# Driver_Mosfet.net
KiCad netlist of a schematic drawn in Altium Designer
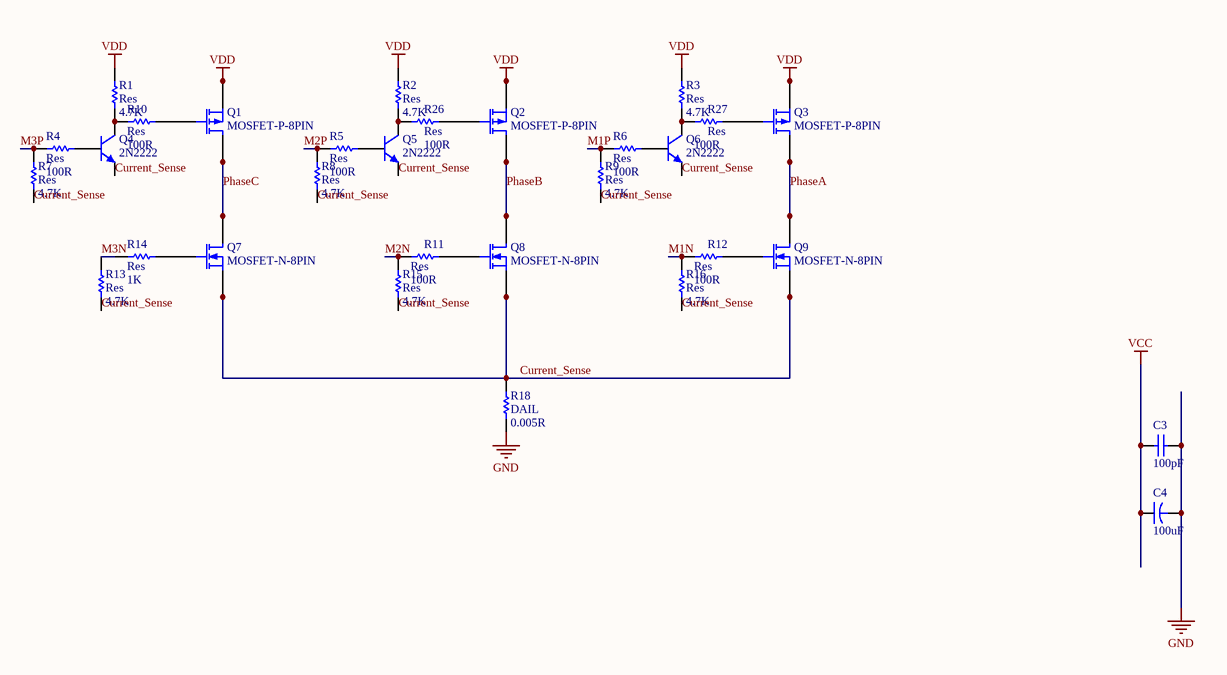
[diagram p0: Driver_Mosfet.SchDoc]

(export (version "E")
  (design (tool "Eeschema 10.0.6"))
  (components
    (comp (ref "C3")
      (value "100pF")
      (footprint "2012[0805]")
      (description "Capacitor")
      (fields (field (name "Comment") "Cap_UP") (field (name "PUBLISHER") "Altium Limited"))
      (libsource (lib "KN2CLib") (part "Cap_UP"))
    )
    (comp (ref "C4")
      (value "100uF")
      (footprint "7343")
      (description "Capacitor")
      (fields (field (name "Comment") "Cap_El") (field (name "PUBLISHER") "Altium Limited"))
      (libsource (lib "KN2CLib") (part "Cap_El"))
    )
    (comp (ref "Q1")
      (value "MOSFET-P-8PIN")
      (footprint "SO-8_N")
      (description "P-Channel MOSFET")
      (fields (field (name "PUBLISHER") "Altium Limited"))
      (libsource (lib "KN2CLib") (part "MOSFET-P-8PIN"))
    )
    (comp (ref "Q2")
      (value "MOSFET-P-8PIN")
      (footprint "SO-8_N")
      (description "P-Channel MOSFET")
      (fields (field (name "PUBLISHER") "Altium Limited"))
      (libsource (lib "KN2CLib") (part "MOSFET-P-8PIN"))
    )
    (comp (ref "Q3")
      (value "MOSFET-P-8PIN")
      (footprint "SO-8_N")
      (description "P-Channel MOSFET")
      (fields (field (name "PUBLISHER") "Altium Limited"))
      (libsource (lib "KN2CLib") (part "MOSFET-P-8PIN"))
    )
    (comp (ref "Q4")
      (value "2N2222")
      (footprint "SOT-23")
      (description "NPN Bipolar Transistor")
      (fields (field (name "PUBLISHER") "Altium Limited"))
      (libsource (lib "KN2CLib") (part "2N2222"))
    )
    (comp (ref "Q5")
      (value "2N2222")
      (footprint "SOT-23")
      (description "NPN Bipolar Transistor")
      (fields (field (name "PUBLISHER") "Altium Limited"))
      (libsource (lib "KN2CLib") (part "2N2222"))
    )
    (comp (ref "Q6")
      (value "2N2222")
      (footprint "SOT-23")
      (description "NPN Bipolar Transistor")
      (fields (field (name "PUBLISHER") "Altium Limited"))
      (libsource (lib "KN2CLib") (part "2N2222"))
    )
    (comp (ref "Q7")
      (value "MOSFET-N-8PIN")
      (footprint "SO-8_N")
      (description "N-Channel MOSFET")
      (fields (field (name "PUBLISHER") "Altium Limited"))
      (libsource (lib "KN2CLib") (part "MOSFET-N-8PIN"))
    )
    (comp (ref "Q8")
      (value "MOSFET-N-8PIN")
      (footprint "SO-8_N")
      (description "N-Channel MOSFET")
      (fields (field (name "PUBLISHER") "Altium Limited"))
      (libsource (lib "KN2CLib") (part "MOSFET-N-8PIN"))
    )
    (comp (ref "Q9")
      (value "MOSFET-N-8PIN")
      (footprint "SO-8_N")
      (description "N-Channel MOSFET")
      (fields (field (name "PUBLISHER") "Altium Limited"))
      (libsource (lib "KN2CLib") (part "MOSFET-N-8PIN"))
    )
    (comp (ref "R1")
      (value "Res")
      (footprint "2012[0805]")
      (description "Semiconductor Resistor")
      (fields (field (name "ALTIUM_VALUE") "4.7K") (field (name "PUBLISHER") "Altium Limited"))
      (libsource (lib "KN2CLib") (part "=Value"))
    )
    (comp (ref "R2")
      (value "Res")
      (footprint "2012[0805]")
      (description "Semiconductor Resistor")
      (fields (field (name "ALTIUM_VALUE") "4.7K") (field (name "PUBLISHER") "Altium Limited"))
      (libsource (lib "KN2CLib") (part "=Value"))
    )
    (comp (ref "R3")
      (value "Res")
      (footprint "2012[0805]")
      (description "Semiconductor Resistor")
      (fields (field (name "ALTIUM_VALUE") "4.7K") (field (name "PUBLISHER") "Altium Limited"))
      (libsource (lib "KN2CLib") (part "=Value"))
    )
    (comp (ref "R4")
      (value "Res")
      (footprint "2012[0805]")
      (description "Semiconductor Resistor")
      (fields (field (name "ALTIUM_VALUE") "100R") (field (name "PUBLISHER") "Altium Limited"))
      (libsource (lib "KN2CLib") (part "=Value"))
    )
    (comp (ref "R5")
      (value "Res")
      (footprint "2012[0805]")
      (description "Semiconductor Resistor")
      (fields (field (name "ALTIUM_VALUE") "100R") (field (name "PUBLISHER") "Altium Limited"))
      (libsource (lib "KN2CLib") (part "=Value"))
    )
    (comp (ref "R6")
      (value "Res")
      (footprint "2012[0805]")
      (description "Semiconductor Resistor")
      (fields (field (name "ALTIUM_VALUE") "100R") (field (name "PUBLISHER") "Altium Limited"))
      (libsource (lib "KN2CLib") (part "=Value"))
    )
    (comp (ref "R7")
      (value "Res")
      (footprint "2012[0805]")
      (description "Semiconductor Resistor")
      (fields (field (name "ALTIUM_VALUE") "4.7K") (field (name "PUBLISHER") "Altium Limited"))
      (libsource (lib "KN2CLib") (part "=Value"))
    )
    (comp (ref "R8")
      (value "Res")
      (footprint "2012[0805]")
      (description "Semiconductor Resistor")
      (fields (field (name "ALTIUM_VALUE") "4.7K") (field (name "PUBLISHER") "Altium Limited"))
      (libsource (lib "KN2CLib") (part "=Value"))
    )
    (comp (ref "R9")
      (value "Res")
      (footprint "2012[0805]")
      (description "Semiconductor Resistor")
      (fields (field (name "ALTIUM_VALUE") "4.7K") (field (name "PUBLISHER") "Altium Limited"))
      (libsource (lib "KN2CLib") (part "=Value"))
    )
    (comp (ref "R10")
      (value "Res")
      (footprint "2012[0805]")
      (description "Semiconductor Resistor")
      (fields (field (name "ALTIUM_VALUE") "100R") (field (name "PUBLISHER") "Altium Limited"))
      (libsource (lib "KN2CLib") (part "=Value"))
    )
    (comp (ref "R11")
      (value "Res")
      (footprint "2012[0805]")
      (description "Semiconductor Resistor")
      (fields (field (name "ALTIUM_VALUE") "100R") (field (name "PUBLISHER") "Altium Limited"))
      (libsource (lib "KN2CLib") (part "=Value"))
    )
    (comp (ref "R12")
      (value "Res")
      (footprint "2012[0805]")
      (description "Semiconductor Resistor")
      (fields (field (name "ALTIUM_VALUE") "100R") (field (name "PUBLISHER") "Altium Limited"))
      (libsource (lib "KN2CLib") (part "=Value"))
    )
    (comp (ref "R13")
      (value "Res")
      (footprint "2012[0805]")
      (description "Semiconductor Resistor")
      (fields (field (name "ALTIUM_VALUE") "4.7K") (field (name "PUBLISHER") "Altium Limited"))
      (libsource (lib "KN2CLib") (part "=Value"))
    )
    (comp (ref "R14")
      (value "Res")
      (footprint "2012[0805]")
      (description "Semiconductor Resistor")
      (fields (field (name "ALTIUM_VALUE") "1K") (field (name "PUBLISHER") "Altium Limited"))
      (libsource (lib "KN2CLib") (part "Res"))
    )
    (comp (ref "R15")
      (value "Res")
      (footprint "2012[0805]")
      (description "Semiconductor Resistor")
      (fields (field (name "ALTIUM_VALUE") "4.7K") (field (name "PUBLISHER") "Altium Limited"))
      (libsource (lib "KN2CLib") (part "=Value"))
    )
    (comp (ref "R16")
      (value "Res")
      (footprint "2012[0805]")
      (description "Semiconductor Resistor")
      (fields (field (name "ALTIUM_VALUE") "4.7K") (field (name "PUBLISHER") "Altium Limited"))
      (libsource (lib "KN2CLib") (part "=Value"))
    )
    (comp (ref "R18")
      (value "DAIL")
      (footprint "6332[2512]")
      (description "Semiconductor Resistor")
      (fields (field (name "ALTIUM_VALUE") "0.005R") (field (name "PUBLISHER") "Altium Limited"))
      (libsource (lib "KN2CLib") (part "Res"))
    )
    (comp (ref "R26")
      (value "Res")
      (footprint "2012[0805]")
      (description "Semiconductor Resistor")
      (fields (field (name "ALTIUM_VALUE") "100R") (field (name "PUBLISHER") "Altium Limited"))
      (libsource (lib "KN2CLib") (part "=Value"))
    )
    (comp (ref "R27")
      (value "Res")
      (footprint "2012[0805]")
      (description "Semiconductor Resistor")
      (fields (field (name "ALTIUM_VALUE") "100R") (field (name "PUBLISHER") "Altium Limited"))
      (libsource (lib "KN2CLib") (part "=Value"))
    )
  )
  (nets
    (net (code "1") (name "/Current_Sense") (class "Default")
      (node (ref "Q4") (pin "3") (pinfunction "E_3") (pintype "passive"))
      (node (ref "Q5") (pin "3") (pinfunction "E_3") (pintype "passive"))
      (node (ref "Q6") (pin "3") (pinfunction "E_3") (pintype "passive"))
      (node (ref "Q7") (pin "1") (pinfunction "S_1") (pintype "passive"))
      (node (ref "Q7") (pin "2") (pinfunction "S_2") (pintype "passive"))
      (node (ref "Q7") (pin "3") (pinfunction "S_3") (pintype "passive"))
      (node (ref "Q8") (pin "1") (pinfunction "S_1") (pintype "passive"))
      (node (ref "Q8") (pin "2") (pinfunction "S_2") (pintype "passive"))
      (node (ref "Q8") (pin "3") (pinfunction "S_3") (pintype "passive"))
      (node (ref "Q9") (pin "1") (pinfunction "S_1") (pintype "passive"))
      (node (ref "Q9") (pin "2") (pinfunction "S_2") (pintype "passive"))
      (node (ref "Q9") (pin "3") (pinfunction "S_3") (pintype "passive"))
      (node (ref "R13") (pin "1") (pinfunction "1_1") (pintype "passive"))
      (node (ref "R15") (pin "1") (pinfunction "1_1") (pintype "passive"))
      (node (ref "R16") (pin "1") (pinfunction "1_1") (pintype "passive"))
      (node (ref "R18") (pin "2") (pinfunction "2_2") (pintype "passive"))
      (node (ref "R7") (pin "1") (pinfunction "1_1") (pintype "passive"))
      (node (ref "R8") (pin "1") (pinfunction "1_1") (pintype "passive"))
      (node (ref "R9") (pin "1") (pinfunction "1_1") (pintype "passive"))
    )
    (net (code "2") (name "/M1N") (class "Default")
      (node (ref "R12") (pin "1") (pinfunction "1_1") (pintype "passive"))
      (node (ref "R16") (pin "2") (pinfunction "2_2") (pintype "passive"))
    )
    (net (code "3") (name "/M1P") (class "Default")
      (node (ref "R6") (pin "2") (pinfunction "2_2") (pintype "passive"))
      (node (ref "R9") (pin "2") (pinfunction "2_2") (pintype "passive"))
    )
    (net (code "4") (name "/M2N") (class "Default")
      (node (ref "R11") (pin "1") (pinfunction "1_1") (pintype "passive"))
      (node (ref "R15") (pin "2") (pinfunction "2_2") (pintype "passive"))
    )
    (net (code "5") (name "/M2P") (class "Default")
      (node (ref "R5") (pin "2") (pinfunction "2_2") (pintype "passive"))
      (node (ref "R8") (pin "2") (pinfunction "2_2") (pintype "passive"))
    )
    (net (code "6") (name "/M3N") (class "Default")
      (node (ref "R13") (pin "2") (pinfunction "2_2") (pintype "passive"))
      (node (ref "R14") (pin "1") (pinfunction "1_1") (pintype "passive"))
    )
    (net (code "7") (name "/M3P") (class "Default")
      (node (ref "R4") (pin "2") (pinfunction "2_2") (pintype "passive"))
      (node (ref "R7") (pin "2") (pinfunction "2_2") (pintype "passive"))
    )
    (net (code "8") (name "/PhaseA") (class "Default")
      (node (ref "Q3") (pin "5") (pinfunction "D_5") (pintype "passive"))
      (node (ref "Q3") (pin "6") (pinfunction "D_6") (pintype "passive"))
      (node (ref "Q3") (pin "7") (pinfunction "D_7") (pintype "passive"))
      (node (ref "Q3") (pin "8") (pinfunction "D_8") (pintype "passive"))
      (node (ref "Q9") (pin "5") (pinfunction "D_5") (pintype "passive"))
      (node (ref "Q9") (pin "6") (pinfunction "D_6") (pintype "passive"))
      (node (ref "Q9") (pin "7") (pinfunction "D_7") (pintype "passive"))
      (node (ref "Q9") (pin "8") (pinfunction "D_8") (pintype "passive"))
    )
    (net (code "9") (name "/PhaseB") (class "Default")
      (node (ref "Q2") (pin "5") (pinfunction "D_5") (pintype "passive"))
      (node (ref "Q2") (pin "6") (pinfunction "D_6") (pintype "passive"))
      (node (ref "Q2") (pin "7") (pinfunction "D_7") (pintype "passive"))
      (node (ref "Q2") (pin "8") (pinfunction "D_8") (pintype "passive"))
      (node (ref "Q8") (pin "5") (pinfunction "D_5") (pintype "passive"))
      (node (ref "Q8") (pin "6") (pinfunction "D_6") (pintype "passive"))
      (node (ref "Q8") (pin "7") (pinfunction "D_7") (pintype "passive"))
      (node (ref "Q8") (pin "8") (pinfunction "D_8") (pintype "passive"))
    )
    (net (code "10") (name "/PhaseC") (class "Default")
      (node (ref "Q1") (pin "5") (pinfunction "D_5") (pintype "passive"))
      (node (ref "Q1") (pin "6") (pinfunction "D_6") (pintype "passive"))
      (node (ref "Q1") (pin "7") (pinfunction "D_7") (pintype "passive"))
      (node (ref "Q1") (pin "8") (pinfunction "D_8") (pintype "passive"))
      (node (ref "Q7") (pin "5") (pinfunction "D_5") (pintype "passive"))
      (node (ref "Q7") (pin "6") (pinfunction "D_6") (pintype "passive"))
      (node (ref "Q7") (pin "7") (pinfunction "D_7") (pintype "passive"))
      (node (ref "Q7") (pin "8") (pinfunction "D_8") (pintype "passive"))
    )
    (net (code "11") (name "GND") (class "Default")
      (node (ref "C3") (pin "2") (pinfunction "2_2") (pintype "passive"))
      (node (ref "C4") (pin "2") (pinfunction "2_2") (pintype "passive"))
      (node (ref "R18") (pin "1") (pinfunction "1_1") (pintype "passive"))
    )
    (net (code "12") (name "Net-(Q1-G)") (class "Default")
      (node (ref "Q1") (pin "4") (pinfunction "G_4") (pintype "passive"))
      (node (ref "R10") (pin "2") (pinfunction "2_2") (pintype "passive"))
    )
    (net (code "13") (name "Net-(Q2-G)") (class "Default")
      (node (ref "Q2") (pin "4") (pinfunction "G_4") (pintype "passive"))
      (node (ref "R26") (pin "2") (pinfunction "2_2") (pintype "passive"))
    )
    (net (code "14") (name "Net-(Q3-G)") (class "Default")
      (node (ref "Q3") (pin "4") (pinfunction "G_4") (pintype "passive"))
      (node (ref "R27") (pin "2") (pinfunction "2_2") (pintype "passive"))
    )
    (net (code "15") (name "Net-(Q4-B)") (class "Default")
      (node (ref "Q4") (pin "2") (pinfunction "B_2") (pintype "passive"))
      (node (ref "R4") (pin "1") (pinfunction "1_1") (pintype "passive"))
    )
    (net (code "16") (name "Net-(Q4-C)") (class "Default")
      (node (ref "Q4") (pin "1") (pinfunction "C_1") (pintype "passive"))
      (node (ref "R1") (pin "1") (pinfunction "1_1") (pintype "passive"))
      (node (ref "R10") (pin "1") (pinfunction "1_1") (pintype "passive"))
    )
    (net (code "17") (name "Net-(Q5-B)") (class "Default")
      (node (ref "Q5") (pin "2") (pinfunction "B_2") (pintype "passive"))
      (node (ref "R5") (pin "1") (pinfunction "1_1") (pintype "passive"))
    )
    (net (code "18") (name "Net-(Q5-C)") (class "Default")
      (node (ref "Q5") (pin "1") (pinfunction "C_1") (pintype "passive"))
      (node (ref "R2") (pin "1") (pinfunction "1_1") (pintype "passive"))
      (node (ref "R26") (pin "1") (pinfunction "1_1") (pintype "passive"))
    )
    (net (code "19") (name "Net-(Q6-B)") (class "Default")
      (node (ref "Q6") (pin "2") (pinfunction "B_2") (pintype "passive"))
      (node (ref "R6") (pin "1") (pinfunction "1_1") (pintype "passive"))
    )
    (net (code "20") (name "Net-(Q6-C)") (class "Default")
      (node (ref "Q6") (pin "1") (pinfunction "C_1") (pintype "passive"))
      (node (ref "R27") (pin "1") (pinfunction "1_1") (pintype "passive"))
      (node (ref "R3") (pin "1") (pinfunction "1_1") (pintype "passive"))
    )
    (net (code "21") (name "Net-(Q7-G)") (class "Default")
      (node (ref "Q7") (pin "4") (pinfunction "G_4") (pintype "passive"))
      (node (ref "R14") (pin "2") (pinfunction "2_2") (pintype "passive"))
    )
    (net (code "22") (name "Net-(Q8-G)") (class "Default")
      (node (ref "Q8") (pin "4") (pinfunction "G_4") (pintype "passive"))
      (node (ref "R11") (pin "2") (pinfunction "2_2") (pintype "passive"))
    )
    (net (code "23") (name "Net-(Q9-G)") (class "Default")
      (node (ref "Q9") (pin "4") (pinfunction "G_4") (pintype "passive"))
      (node (ref "R12") (pin "2") (pinfunction "2_2") (pintype "passive"))
    )
    (net (code "24") (name "VCC") (class "Default")
      (node (ref "C3") (pin "1") (pinfunction "1_1") (pintype "passive"))
      (node (ref "C4") (pin "1") (pinfunction "1_1") (pintype "passive"))
    )
    (net (code "25") (name "VDD") (class "Default")
      (node (ref "Q1") (pin "1") (pinfunction "S_1") (pintype "passive"))
      (node (ref "Q1") (pin "2") (pinfunction "S_2") (pintype "passive"))
      (node (ref "Q1") (pin "3") (pinfunction "S_3") (pintype "passive"))
      (node (ref "Q2") (pin "1") (pinfunction "S_1") (pintype "passive"))
      (node (ref "Q2") (pin "2") (pinfunction "S_2") (pintype "passive"))
      (node (ref "Q2") (pin "3") (pinfunction "S_3") (pintype "passive"))
      (node (ref "Q3") (pin "1") (pinfunction "S_1") (pintype "passive"))
      (node (ref "Q3") (pin "2") (pinfunction "S_2") (pintype "passive"))
      (node (ref "Q3") (pin "3") (pinfunction "S_3") (pintype "passive"))
      (node (ref "R1") (pin "2") (pinfunction "2_2") (pintype "passive"))
      (node (ref "R2") (pin "2") (pinfunction "2_2") (pintype "passive"))
      (node (ref "R3") (pin "2") (pinfunction "2_2") (pintype "passive"))
    )
  )
)
